# power.net
KiCad netlist of a schematic drawn in Altium Designer
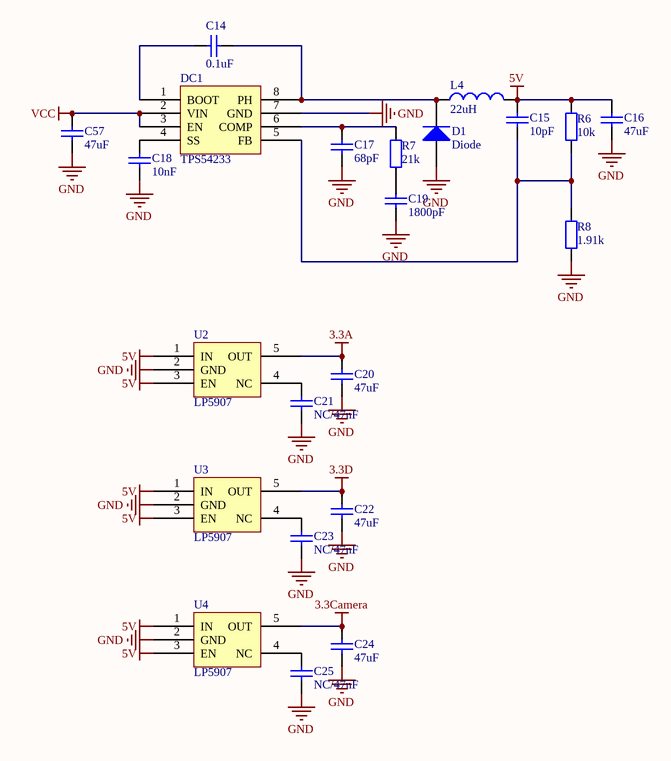
[diagram p0: power.SchDoc]

(export (version "E")
  (design (tool "Eeschema 10.0.6"))
  (components
    (comp (ref "C14")
      (value "0.1uF")
      (footprint "0402")
      (description "Capacitor")
      (fields (field (name "Comment") "Cap") (field (name "PUBLISHER") "Altium Limited"))
      (libsource (lib "RTC6705") (part "Cap"))
    )
    (comp (ref "C15")
      (value "10pF")
      (footprint "0402")
      (description "Capacitor")
      (fields (field (name "Comment") "Cap") (field (name "PUBLISHER") "Altium Limited"))
      (libsource (lib "RTC6705") (part "Cap"))
    )
    (comp (ref "C16")
      (value "47uF")
      (footprint "1210")
      (description "Capacitor")
      (fields (field (name "Comment") "Cap") (field (name "PUBLISHER") "Altium Limited"))
      (libsource (lib "RTC6705") (part "Cap"))
    )
    (comp (ref "C17")
      (value "68pF")
      (footprint "0402")
      (description "Capacitor")
      (fields (field (name "Comment") "Cap") (field (name "PUBLISHER") "Altium Limited"))
      (libsource (lib "RTC6705") (part "Cap"))
    )
    (comp (ref "C18")
      (value "10nF")
      (footprint "0402")
      (description "Capacitor")
      (fields (field (name "Comment") "Cap") (field (name "PUBLISHER") "Altium Limited"))
      (libsource (lib "RTC6705") (part "Cap"))
    )
    (comp (ref "C19")
      (value "1800pF")
      (footprint "0402")
      (description "Capacitor")
      (fields (field (name "Comment") "Cap") (field (name "PUBLISHER") "Altium Limited"))
      (libsource (lib "RTC6705") (part "Cap"))
    )
    (comp (ref "C20")
      (value "47uF")
      (footprint "0805")
      (description "Capacitor")
      (fields (field (name "Comment") "Cap") (field (name "PUBLISHER") "Altium Limited"))
      (libsource (lib "RTC6705") (part "Cap"))
    )
    (comp (ref "C21")
      (value "NC/47nF")
      (footprint "0402")
      (description "Capacitor")
      (fields (field (name "Comment") "Cap") (field (name "PUBLISHER") "Altium Limited"))
      (libsource (lib "RTC6705") (part "Cap"))
    )
    (comp (ref "C22")
      (value "47uF")
      (footprint "0805")
      (description "Capacitor")
      (fields (field (name "Comment") "Cap") (field (name "PUBLISHER") "Altium Limited"))
      (libsource (lib "RTC6705") (part "Cap"))
    )
    (comp (ref "C23")
      (value "NC/47nF")
      (footprint "0402")
      (description "Capacitor")
      (fields (field (name "Comment") "Cap") (field (name "PUBLISHER") "Altium Limited"))
      (libsource (lib "RTC6705") (part "Cap"))
    )
    (comp (ref "C24")
      (value "47uF")
      (footprint "0805")
      (description "Capacitor")
      (fields (field (name "Comment") "Cap") (field (name "PUBLISHER") "Altium Limited"))
      (libsource (lib "RTC6705") (part "Cap"))
    )
    (comp (ref "C25")
      (value "NC/47nF")
      (footprint "0402")
      (description "Capacitor")
      (fields (field (name "Comment") "Cap") (field (name "PUBLISHER") "Altium Limited"))
      (libsource (lib "RTC6705") (part "Cap"))
    )
    (comp (ref "C57")
      (value "47uF")
      (footprint "1210")
      (description "Capacitor")
      (fields (field (name "Comment") "Cap") (field (name "PUBLISHER") "Altium Limited"))
      (libsource (lib "RTC6705") (part "Cap"))
    )
    (comp (ref "D1")
      (value "Diode")
      (footprint "SMC")
      (description "Default Diode")
      (fields (field (name "PUBLISHER") "Altium Limited"))
      (libsource (lib "Miscellaneous Devices") (part "Diode"))
    )
    (comp (ref "DC1") (value "TPS54233") (footprint "SO8") (libsource (lib "RTC6705") (part "TPS54233")))
    (comp (ref "L4")
      (value "22uH")
      (footprint "L6028/L6045")
      (description "Inductor")
      (fields (field (name "PUBLISHER") "Altium Limited"))
      (libsource (lib "Miscellaneous Devices") (part "Inductor"))
    )
    (comp (ref "R6")
      (value "10k")
      (footprint "0402")
      (description "Resistor")
      (fields (field (name "Comment") "Res2") (field (name "PUBLISHER") "Altium Limited"))
      (libsource (lib "RTC6705") (part "Res2"))
    )
    (comp (ref "R7")
      (value "21k")
      (footprint "0402")
      (description "Resistor")
      (fields (field (name "Comment") "Res2") (field (name "PUBLISHER") "Altium Limited"))
      (libsource (lib "RTC6705") (part "Res2"))
    )
    (comp (ref "R8")
      (value "1.91k")
      (footprint "0402")
      (description "Resistor")
      (fields (field (name "Comment") "Res2") (field (name "PUBLISHER") "Altium Limited"))
      (libsource (lib "RTC6705") (part "Res2"))
    )
    (comp (ref "U2") (value "LP5907") (footprint "SOT23-5") (libsource (lib "RTC6705") (part "LP5907")))
    (comp (ref "U3") (value "LP5907") (footprint "SOT23-5") (libsource (lib "RTC6705") (part "LP5907")))
    (comp (ref "U4") (value "LP5907") (footprint "SOT23-5") (libsource (lib "RTC6705") (part "LP5907")))
  )
  (nets
    (net (code "1") (name "3.3A") (class "Default")
      (node (ref "C20") (pin "1") (pinfunction "1_1") (pintype "passive"))
      (node (ref "U2") (pin "5") (pinfunction "OUT_5") (pintype "passive"))
    )
    (net (code "2") (name "3.3Camera") (class "Default")
      (node (ref "C24") (pin "1") (pinfunction "1_1") (pintype "passive"))
      (node (ref "U4") (pin "5") (pinfunction "OUT_5") (pintype "passive"))
    )
    (net (code "3") (name "3.3D") (class "Default")
      (node (ref "C22") (pin "1") (pinfunction "1_1") (pintype "passive"))
      (node (ref "U3") (pin "5") (pinfunction "OUT_5") (pintype "passive"))
    )
    (net (code "4") (name "5V") (class "Default")
      (node (ref "C15") (pin "1") (pinfunction "1_1") (pintype "passive"))
      (node (ref "C16") (pin "1") (pinfunction "1_1") (pintype "passive"))
      (node (ref "L4") (pin "2") (pinfunction "2_2") (pintype "passive"))
      (node (ref "R6") (pin "1") (pinfunction "1_1") (pintype "passive"))
      (node (ref "U2") (pin "1") (pinfunction "IN_1") (pintype "passive"))
      (node (ref "U2") (pin "3") (pinfunction "EN_3") (pintype "passive"))
      (node (ref "U3") (pin "1") (pinfunction "IN_1") (pintype "passive"))
      (node (ref "U3") (pin "3") (pinfunction "EN_3") (pintype "passive"))
      (node (ref "U4") (pin "1") (pinfunction "IN_1") (pintype "passive"))
      (node (ref "U4") (pin "3") (pinfunction "EN_3") (pintype "passive"))
    )
    (net (code "5") (name "GND") (class "Default")
      (node (ref "C16") (pin "2") (pinfunction "2_2") (pintype "passive"))
      (node (ref "C17") (pin "2") (pinfunction "2_2") (pintype "passive"))
      (node (ref "C18") (pin "2") (pinfunction "2_2") (pintype "passive"))
      (node (ref "C19") (pin "2") (pinfunction "2_2") (pintype "passive"))
      (node (ref "C20") (pin "2") (pinfunction "2_2") (pintype "passive"))
      (node (ref "C21") (pin "2") (pinfunction "2_2") (pintype "passive"))
      (node (ref "C22") (pin "2") (pinfunction "2_2") (pintype "passive"))
      (node (ref "C23") (pin "2") (pinfunction "2_2") (pintype "passive"))
      (node (ref "C24") (pin "2") (pinfunction "2_2") (pintype "passive"))
      (node (ref "C25") (pin "2") (pinfunction "2_2") (pintype "passive"))
      (node (ref "C57") (pin "2") (pinfunction "2_2") (pintype "passive"))
      (node (ref "D1") (pin "1") (pinfunction "A_1") (pintype "passive"))
      (node (ref "DC1") (pin "7") (pinfunction "GND_7") (pintype "passive"))
      (node (ref "R8") (pin "2") (pinfunction "2_2") (pintype "passive"))
      (node (ref "U2") (pin "2") (pinfunction "GND_2") (pintype "passive"))
      (node (ref "U3") (pin "2") (pinfunction "GND_2") (pintype "passive"))
      (node (ref "U4") (pin "2") (pinfunction "GND_2") (pintype "passive"))
    )
    (net (code "6") (name "Net-(C19-Pad1)") (class "Default")
      (node (ref "C19") (pin "1") (pinfunction "1_1") (pintype "passive"))
      (node (ref "R7") (pin "2") (pinfunction "2_2") (pintype "passive"))
    )
    (net (code "7") (name "Net-(D1-K)") (class "Default")
      (node (ref "C14") (pin "1") (pinfunction "1_1") (pintype "passive"))
      (node (ref "D1") (pin "2") (pinfunction "K_2") (pintype "passive"))
      (node (ref "DC1") (pin "8") (pinfunction "PH_8") (pintype "passive"))
      (node (ref "L4") (pin "1") (pinfunction "1_1") (pintype "passive"))
    )
    (net (code "8") (name "Net-(DC1-BOOT)") (class "Default")
      (node (ref "C14") (pin "2") (pinfunction "2_2") (pintype "passive"))
      (node (ref "DC1") (pin "1") (pinfunction "BOOT_1") (pintype "passive"))
    )
    (net (code "9") (name "Net-(DC1-COMP)") (class "Default")
      (node (ref "C17") (pin "1") (pinfunction "1_1") (pintype "passive"))
      (node (ref "DC1") (pin "6") (pinfunction "COMP_6") (pintype "passive"))
      (node (ref "R7") (pin "1") (pinfunction "1_1") (pintype "passive"))
    )
    (net (code "10") (name "Net-(DC1-FB)") (class "Default")
      (node (ref "C15") (pin "2") (pinfunction "2_2") (pintype "passive"))
      (node (ref "DC1") (pin "5") (pinfunction "FB_5") (pintype "passive"))
      (node (ref "R6") (pin "2") (pinfunction "2_2") (pintype "passive"))
      (node (ref "R8") (pin "1") (pinfunction "1_1") (pintype "passive"))
    )
    (net (code "11") (name "Net-(DC1-SS)") (class "Default")
      (node (ref "C18") (pin "1") (pinfunction "1_1") (pintype "passive"))
      (node (ref "DC1") (pin "4") (pinfunction "SS_4") (pintype "passive"))
    )
    (net (code "12") (name "Net-(U2-NC)") (class "Default")
      (node (ref "C21") (pin "1") (pinfunction "1_1") (pintype "passive"))
      (node (ref "U2") (pin "4") (pinfunction "NC_4") (pintype "passive"))
    )
    (net (code "13") (name "Net-(U3-NC)") (class "Default")
      (node (ref "C23") (pin "1") (pinfunction "1_1") (pintype "passive"))
      (node (ref "U3") (pin "4") (pinfunction "NC_4") (pintype "passive"))
    )
    (net (code "14") (name "Net-(U4-NC)") (class "Default")
      (node (ref "C25") (pin "1") (pinfunction "1_1") (pintype "passive"))
      (node (ref "U4") (pin "4") (pinfunction "NC_4") (pintype "passive"))
    )
    (net (code "15") (name "VCC") (class "Default")
      (node (ref "C57") (pin "1") (pinfunction "1_1") (pintype "passive"))
      (node (ref "DC1") (pin "2") (pinfunction "VIN_2") (pintype "passive"))
      (node (ref "DC1") (pin "3") (pinfunction "EN_3") (pintype "passive"))
    )
  )
)
